# MCU.net
KiCad netlist of a schematic drawn in Altium Designer
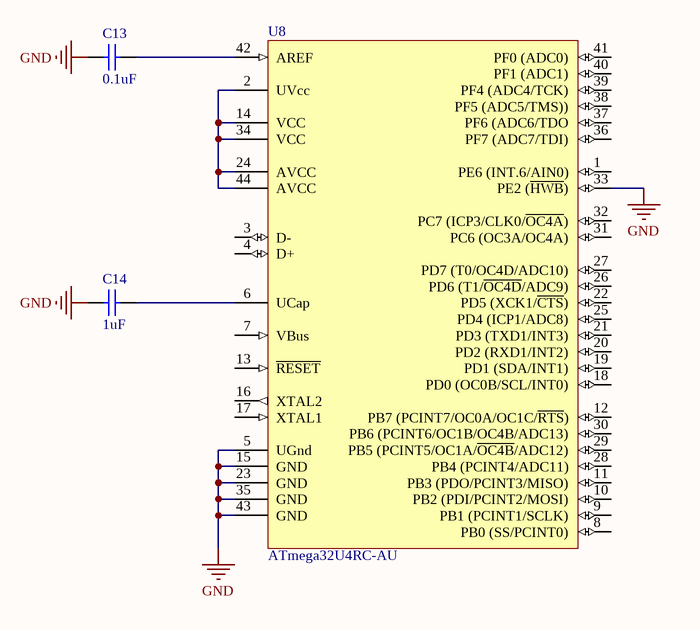
[diagram p0: MCU.SchDoc]

(export (version "E")
  (design (tool "Eeschema 10.0.6"))
  (components
    (comp (ref "C13")
      (value "0.1uF")
      (footprint "1608[0603]")
      (description "Capacitor (Semiconductor SIM Model)")
      (fields (field (name "Comment") "Cap Semi") (field (name "PUBLISHER") "Altium Limited"))
      (libsource (lib "Miscellaneous Devices") (part "Cap Semi"))
    )
    (comp (ref "C14")
      (value "1uF")
      (footprint "1608[0603]")
      (description "Capacitor (Semiconductor SIM Model)")
      (fields (field (name "Comment") "Cap Semi") (field (name "PUBLISHER") "Altium Limited"))
      (libsource (lib "Miscellaneous Devices") (part "Cap Semi"))
    )
    (comp (ref "U8")
      (value "ATmega32U4RC-AU")
      (footprint "44ML_N")
      (libsource (lib "Altium Content Vault") (part "MC-8B-ATM16U4-SQ44"))
    )
  )
  (nets
    (net (code "1") (name "GND") (class "Default")
      (node (ref "C13") (pin "1") (pinfunction "1_1") (pintype "passive"))
      (node (ref "C14") (pin "1") (pinfunction "1_1") (pintype "passive"))
      (node (ref "U8") (pin "15") (pinfunction "GND_15") (pintype "power_in"))
      (node (ref "U8") (pin "23") (pinfunction "GND_23") (pintype "power_in"))
      (node (ref "U8") (pin "33") (pinfunction "PE2_(~{HWB})_33") (pintype "bidirectional"))
      (node (ref "U8") (pin "35") (pinfunction "GND_35") (pintype "power_in"))
      (node (ref "U8") (pin "43") (pinfunction "GND_43") (pintype "power_in"))
      (node (ref "U8") (pin "5") (pinfunction "UGnd_5") (pintype "power_in"))
    )
    (net (code "2") (name "Net-(U8-AREF)") (class "Default")
      (node (ref "C13") (pin "2") (pinfunction "2_2") (pintype "passive"))
      (node (ref "U8") (pin "42") (pinfunction "AREF_42") (pintype "input"))
    )
    (net (code "3") (name "Net-(U8-UCap)") (class "Default")
      (node (ref "C14") (pin "2") (pinfunction "2_2") (pintype "passive"))
      (node (ref "U8") (pin "6") (pinfunction "UCap_6") (pintype "passive"))
    )
    (net (code "4") (name "Net-(U8-UVcc)") (class "Default")
      (node (ref "U8") (pin "14") (pinfunction "VCC_14") (pintype "power_in"))
      (node (ref "U8") (pin "2") (pinfunction "UVcc_2") (pintype "power_in"))
      (node (ref "U8") (pin "24") (pinfunction "AVCC_24") (pintype "power_in"))
      (node (ref "U8") (pin "34") (pinfunction "VCC_34") (pintype "power_in"))
      (node (ref "U8") (pin "44") (pinfunction "AVCC_44") (pintype "power_in"))
    )
    (net (code "5") (name "unconnected-(U8-D+-Pad4)") (class "Default")
      (node (ref "U8") (pin "4") (pinfunction "D+_4") (pintype "bidirectional"))
    )
    (net (code "6") (name "unconnected-(U8-D--Pad3)") (class "Default")
      (node (ref "U8") (pin "3") (pinfunction "D-_3") (pintype "bidirectional"))
    )
    (net (code "7") (name "unconnected-(U8-PB0_(SS{slash}PCINT0)-Pad8)") (class "Default")
      (node (ref "U8") (pin "8") (pinfunction "PB0_(SS/PCINT0)_8") (pintype "bidirectional"))
    )
    (net (code "8") (name "unconnected-(U8-PB1_(PCINT1{slash}SCLK)-Pad9)") (class "Default")
      (node (ref "U8") (pin "9") (pinfunction "PB1_(PCINT1/SCLK)_9") (pintype "bidirectional"))
    )
    (net (code "9") (name "unconnected-(U8-PB2_(PDI{slash}PCINT2{slash}MOSI)-Pad10)") (class "Default")
      (node (ref "U8") (pin "10") (pinfunction "PB2_(PDI/PCINT2/MOSI)_10") (pintype "bidirectional"))
    )
    (net (code "10") (name "unconnected-(U8-PB3_(PDO{slash}PCINT3{slash}MISO)-Pad11)") (class "Default")
      (node (ref "U8") (pin "11") (pinfunction "PB3_(PDO/PCINT3/MISO)_11") (pintype "bidirectional"))
    )
    (net (code "11") (name "unconnected-(U8-PB4_(PCINT4{slash}ADC11)-Pad28)") (class "Default")
      (node (ref "U8") (pin "28") (pinfunction "PB4_(PCINT4/ADC11)_28") (pintype "bidirectional"))
    )
    (net (code "12") (name "unconnected-(U8-PB5_(PCINT5{slash}OC1A{slash}~{OC4B}{slash}ADC12)-Pad29)") (class "Default")
      (node (ref "U8") (pin "29") (pinfunction "PB5_(PCINT5/OC1A/~{OC4B}/ADC12)_29") (pintype "bidirectional"))
    )
    (net (code "13") (name "unconnected-(U8-PB6_(PCINT6{slash}OC1B{slash}OC4B{slash}ADC13)-Pad30)") (class "Default")
      (node (ref "U8") (pin "30") (pinfunction "PB6_(PCINT6/OC1B/OC4B/ADC13)_30") (pintype "bidirectional"))
    )
    (net (code "14") (name "unconnected-(U8-PB7_(PCINT7{slash}OC0A{slash}OC1C{slash}~{RTS})-Pad12)") (class "Default")
      (node (ref "U8") (pin "12") (pinfunction "PB7_(PCINT7/OC0A/OC1C/~{RTS})_12") (pintype "bidirectional"))
    )
    (net (code "15") (name "unconnected-(U8-PC6_(OC3A{slash}OC4A)-Pad31)") (class "Default")
      (node (ref "U8") (pin "31") (pinfunction "PC6_(OC3A/OC4A)_31") (pintype "bidirectional"))
    )
    (net (code "16") (name "unconnected-(U8-PC7_(ICP3{slash}CLK0{slash}~{OC4A})-Pad32)") (class "Default")
      (node (ref "U8") (pin "32") (pinfunction "PC7_(ICP3/CLK0/~{OC4A})_32") (pintype "bidirectional"))
    )
    (net (code "17") (name "unconnected-(U8-PD0_(OC0B{slash}SCL{slash}INT0)-Pad18)") (class "Default")
      (node (ref "U8") (pin "18") (pinfunction "PD0_(OC0B/SCL/INT0)_18") (pintype "bidirectional"))
    )
    (net (code "18") (name "unconnected-(U8-PD1_(SDA{slash}INT1)-Pad19)") (class "Default")
      (node (ref "U8") (pin "19") (pinfunction "PD1_(SDA/INT1)_19") (pintype "bidirectional"))
    )
    (net (code "19") (name "unconnected-(U8-PD2_(RXD1{slash}INT2)-Pad20)") (class "Default")
      (node (ref "U8") (pin "20") (pinfunction "PD2_(RXD1/INT2)_20") (pintype "bidirectional"))
    )
    (net (code "20") (name "unconnected-(U8-PD3_(TXD1{slash}INT3)-Pad21)") (class "Default")
      (node (ref "U8") (pin "21") (pinfunction "PD3_(TXD1/INT3)_21") (pintype "bidirectional"))
    )
    (net (code "21") (name "unconnected-(U8-PD4_(ICP1{slash}ADC8)-Pad25)") (class "Default")
      (node (ref "U8") (pin "25") (pinfunction "PD4_(ICP1/ADC8)_25") (pintype "bidirectional"))
    )
    (net (code "22") (name "unconnected-(U8-PD5_(XCK1{slash}~{CTS})-Pad22)") (class "Default")
      (node (ref "U8") (pin "22") (pinfunction "PD5_(XCK1/~{CTS})_22") (pintype "bidirectional"))
    )
    (net (code "23") (name "unconnected-(U8-PD6_(T1{slash}~{OC4D}{slash}ADC9)-Pad26)") (class "Default")
      (node (ref "U8") (pin "26") (pinfunction "PD6_(T1/~{OC4D}/ADC9)_26") (pintype "bidirectional"))
    )
    (net (code "24") (name "unconnected-(U8-PD7_(T0{slash}OC4D{slash}ADC10)-Pad27)") (class "Default")
      (node (ref "U8") (pin "27") (pinfunction "PD7_(T0/OC4D/ADC10)_27") (pintype "bidirectional"))
    )
    (net (code "25") (name "unconnected-(U8-PE6_(INT.6{slash}AIN0)-Pad1)") (class "Default")
      (node (ref "U8") (pin "1") (pinfunction "PE6_(INT.6/AIN0)_1") (pintype "bidirectional"))
    )
    (net (code "26") (name "unconnected-(U8-PF0_(ADC0)-Pad41)") (class "Default")
      (node (ref "U8") (pin "41") (pinfunction "PF0_(ADC0)_41") (pintype "bidirectional"))
    )
    (net (code "27") (name "unconnected-(U8-PF1_(ADC1)-Pad40)") (class "Default")
      (node (ref "U8") (pin "40") (pinfunction "PF1_(ADC1)_40") (pintype "bidirectional"))
    )
    (net (code "28") (name "unconnected-(U8-PF4_(ADC4{slash}TCK)-Pad39)") (class "Default")
      (node (ref "U8") (pin "39") (pinfunction "PF4_(ADC4/TCK)_39") (pintype "bidirectional"))
    )
    (net (code "29") (name "unconnected-(U8-PF5_(ADC5{slash}TMS))-Pad38)") (class "Default")
      (node (ref "U8") (pin "38") (pinfunction "PF5_(ADC5/TMS))_38") (pintype "bidirectional"))
    )
    (net (code "30") (name "unconnected-(U8-PF6_(ADC6{slash}TDO-Pad37)") (class "Default")
      (node (ref "U8") (pin "37") (pinfunction "PF6_(ADC6/TDO_37") (pintype "bidirectional"))
    )
    (net (code "31") (name "unconnected-(U8-PF7_(ADC7{slash}TDI)-Pad36)") (class "Default")
      (node (ref "U8") (pin "36") (pinfunction "PF7_(ADC7/TDI)_36") (pintype "bidirectional"))
    )
    (net (code "32") (name "unconnected-(U8-VBus-Pad7)") (class "Default")
      (node (ref "U8") (pin "7") (pinfunction "VBus_7") (pintype "input"))
    )
    (net (code "33") (name "unconnected-(U8-XTAL1-Pad17)") (class "Default")
      (node (ref "U8") (pin "17") (pinfunction "XTAL1_17") (pintype "input"))
    )
    (net (code "34") (name "unconnected-(U8-XTAL2-Pad16)") (class "Default")
      (node (ref "U8") (pin "16") (pinfunction "XTAL2_16") (pintype "output"))
    )
    (net (code "35") (name "unconnected-(U8-~{RESET}-Pad13)") (class "Default")
      (node (ref "U8") (pin "13") (pinfunction "~{RESET}_13") (pintype "input"))
    )
  )
)
